# LTC3528.net
KiCad netlist of a schematic drawn in EAGLE
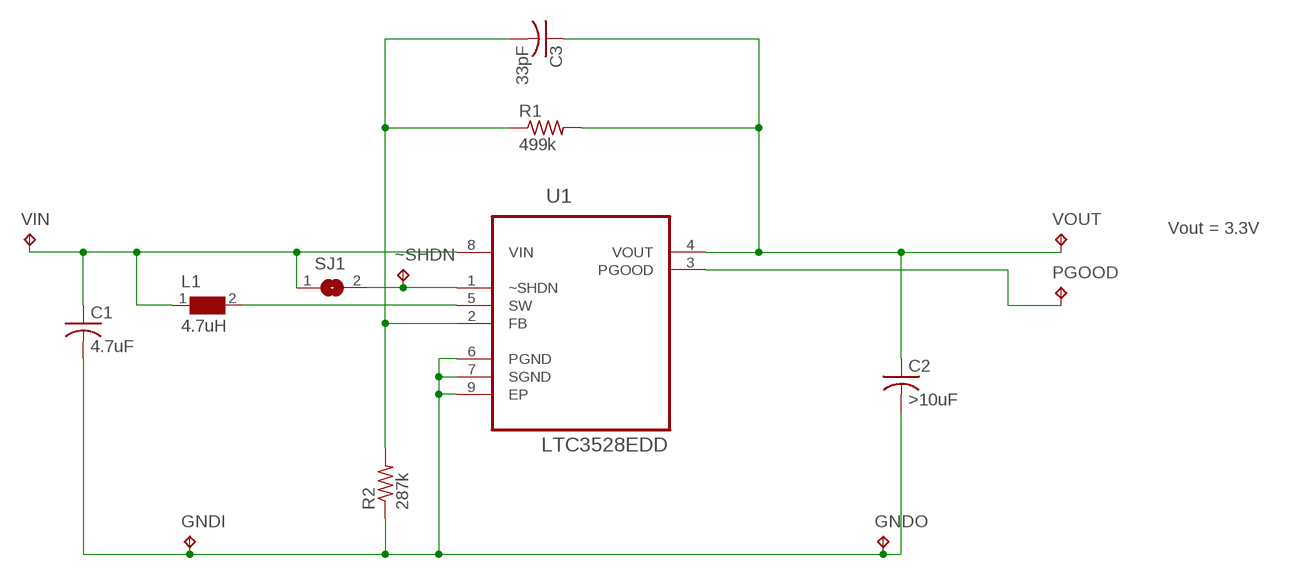
[diagram p0: schematic, sheet 1]

(export (version "E")
  (design (tool "Eeschema 10.0.6"))
  (components
    (comp (ref "C1")
      (value "4.7uF")
      (footprint "eagle-import:C0603")
      (libsource (lib "eagle-import") (part "C-USC0603"))
    )
    (comp (ref "C2")
      (value ">10uF")
      (footprint "eagle-import:C0603")
      (libsource (lib "eagle-import") (part "C-USC0603"))
    )
    (comp (ref "C3")
      (value "33pF")
      (footprint "eagle-import:C0603")
      (libsource (lib "eagle-import") (part "C-USC0603"))
    )
    (comp (ref "GNDI")
      (value "TPPAD1-13")
      (footprint "eagle-import:P1-13")
      (libsource (lib "eagle-import") (part "TPPAD1-13"))
    )
    (comp (ref "GNDO")
      (value "TPPAD1-13")
      (footprint "eagle-import:P1-13")
      (libsource (lib "eagle-import") (part "TPPAD1-13"))
    )
    (comp (ref "L1")
      (value "4.7uH")
      (footprint "eagle-import:WE-TPC_2828")
      (fields (field (name "MPN") "74402500047 "))
      (libsource (lib "eagle-import") (part "WE-TPC_2828-74402500047"))
    )
    (comp (ref "PGOOD")
      (value "TPPAD1-13")
      (footprint "eagle-import:P1-13")
      (fields (field (name "TP_SIGNAL_NAME") "PGOOD"))
      (libsource (lib "eagle-import") (part "TPPAD1-13"))
    )
    (comp (ref "R1")
      (value "499k")
      (footprint "eagle-import:R0603")
      (libsource (lib "eagle-import") (part "R-US_R0603"))
    )
    (comp (ref "R2")
      (value "287k")
      (footprint "eagle-import:R0603")
      (libsource (lib "eagle-import") (part "R-US_R0603"))
    )
    (comp (ref "SJ1")
      (value "not SHDN")
      (footprint "eagle-import:SJ")
      (libsource (lib "eagle-import") (part "SJ"))
    )
    (comp (ref "U1")
      (value "LTC3528EDD")
      (footprint "eagle-import:DFN300X200X80-9N")
      (fields (field (name "MPN") "LTC3528EDDB-2#PBF"))
      (libsource (lib "eagle-import") (part "LTC3528EDDB-2PBF"))
    )
    (comp (ref "VIN")
      (value "TPPAD1-13")
      (footprint "eagle-import:P1-13")
      (fields (field (name "TP_SIGNAL_NAME") "VIN"))
      (libsource (lib "eagle-import") (part "TPPAD1-13"))
    )
    (comp (ref "VOUT")
      (value "TPPAD1-13")
      (footprint "eagle-import:P1-13")
      (fields (field (name "TP_SIGNAL_NAME") "VOUT"))
      (libsource (lib "eagle-import") (part "TPPAD1-13"))
    )
    (comp (ref "~SHDN")
      (value "TPPAD1-13")
      (footprint "eagle-import:P1-13")
      (libsource (lib "eagle-import") (part "TPPAD1-13"))
    )
  )
  (nets
    (net (code "1") (name "Net-(U1-EP)") (class "Default")
      (node (ref "C1") (pin "2") (pinfunction "2_2") (pintype "passive"))
      (node (ref "C2") (pin "2") (pinfunction "2_2") (pintype "passive"))
      (node (ref "GNDI") (pin "TP") (pinfunction "TP_TP") (pintype "input"))
      (node (ref "GNDO") (pin "TP") (pinfunction "TP_TP") (pintype "input"))
      (node (ref "R2") (pin "1") (pinfunction "1_1") (pintype "passive"))
      (node (ref "U1") (pin "6") (pinfunction "PGND_6") (pintype "passive"))
      (node (ref "U1") (pin "7") (pinfunction "SGND_7") (pintype "passive"))
      (node (ref "U1") (pin "9") (pinfunction "EP_9") (pintype "passive"))
    )
    (net (code "2") (name "Net-(U1-FB)") (class "Default")
      (node (ref "C3") (pin "2") (pinfunction "2_2") (pintype "passive"))
      (node (ref "R1") (pin "1") (pinfunction "1_1") (pintype "passive"))
      (node (ref "R2") (pin "2") (pinfunction "2_2") (pintype "passive"))
      (node (ref "U1") (pin "2") (pinfunction "FB_2") (pintype "input"))
    )
    (net (code "3") (name "Net-(U1-PGOOD)") (class "Default")
      (node (ref "PGOOD") (pin "TP") (pinfunction "TP_TP") (pintype "input"))
      (node (ref "U1") (pin "3") (pinfunction "PGOOD_3") (pintype "output"))
    )
    (net (code "4") (name "Net-(U1-SW)") (class "Default")
      (node (ref "L1") (pin "2") (pinfunction "2_2") (pintype "passive"))
      (node (ref "U1") (pin "5") (pinfunction "SW_5") (pintype "passive"))
    )
    (net (code "5") (name "Net-(U1-VIN)") (class "Default")
      (node (ref "C1") (pin "1") (pinfunction "1_1") (pintype "passive"))
      (node (ref "L1") (pin "1") (pinfunction "1_1") (pintype "passive"))
      (node (ref "SJ1") (pin "1") (pinfunction "1_1") (pintype "passive"))
      (node (ref "U1") (pin "8") (pinfunction "VIN_8") (pintype "power_in"))
      (node (ref "VIN") (pin "TP") (pinfunction "TP_TP") (pintype "input"))
    )
    (net (code "6") (name "Net-(U1-VOUT)") (class "Default")
      (node (ref "C2") (pin "1") (pinfunction "1_1") (pintype "passive"))
      (node (ref "C3") (pin "1") (pinfunction "1_1") (pintype "passive"))
      (node (ref "R1") (pin "2") (pinfunction "2_2") (pintype "passive"))
      (node (ref "U1") (pin "4") (pinfunction "VOUT_4") (pintype "output"))
      (node (ref "VOUT") (pin "TP") (pinfunction "TP_TP") (pintype "input"))
    )
    (net (code "7") (name "Net-(U1-~{SHDN})") (class "Default")
      (node (ref "SJ1") (pin "2") (pinfunction "2_2") (pintype "passive"))
      (node (ref "U1") (pin "1") (pinfunction "~{SHDN}_1") (pintype "input"))
      (node (ref "~SHDN") (pin "TP") (pinfunction "TP_TP") (pintype "input"))
    )
  )
)
